# Digit.net
KiCad netlist of a schematic drawn in Altium Designer
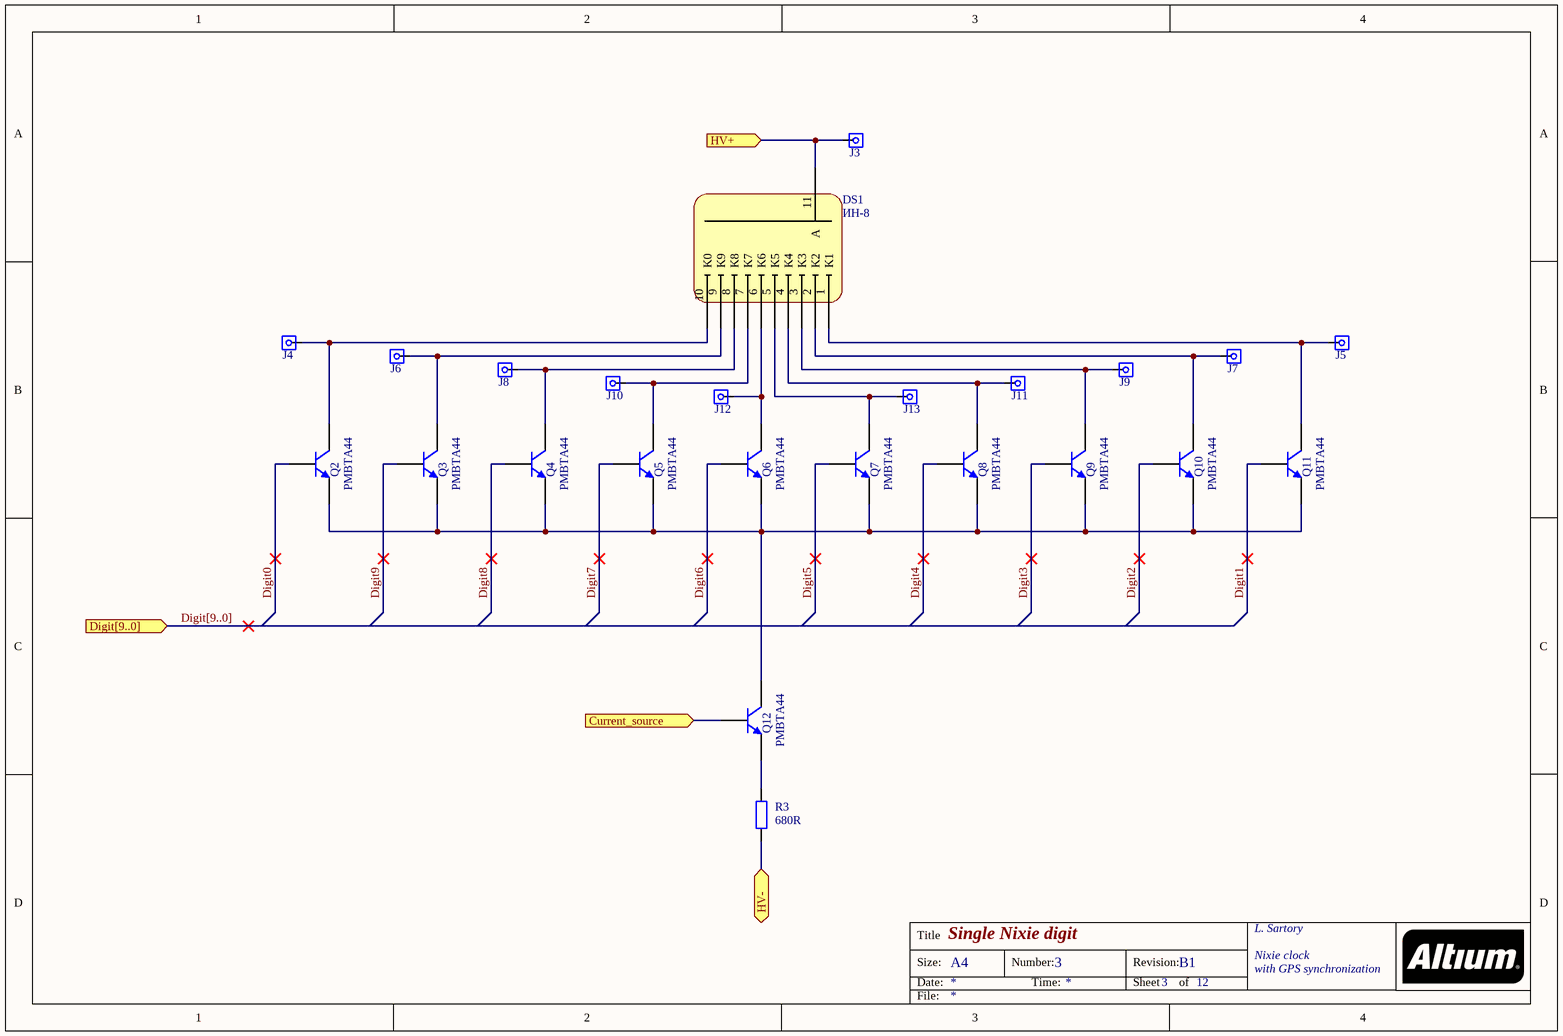
[diagram p0: Digit.SchDoc]

(export (version "E")
  (design (tool "Eeschema 10.0.6"))
  (components
    (comp (ref "DS1")
      (value "ИН-8")
      (footprint "IN-8")
      (description "Nixie tube")
      (libsource (lib "Nixie") (part "ИН-8"))
    )
    (comp (ref "J3")
      (value "TE_5645518-1")
      (footprint "TE_5645518-1")
      (description "Mini-spring socket")
      (libsource (lib "") (part "TE_5645518-1_1"))
    )
    (comp (ref "J4")
      (value "TE_5645518-1")
      (footprint "TE_5645518-1")
      (description "Mini-spring socket")
      (libsource (lib "Nixie") (part "TE_5645518-1"))
    )
    (comp (ref "J5")
      (value "TE_5645518-1")
      (footprint "TE_5645518-1")
      (description "Mini-spring socket")
      (libsource (lib "") (part "TE_5645518-1_1"))
    )
    (comp (ref "J6")
      (value "TE_5645518-1")
      (footprint "TE_5645518-1")
      (description "Mini-spring socket")
      (libsource (lib "Nixie") (part "TE_5645518-1"))
    )
    (comp (ref "J7")
      (value "TE_5645518-1")
      (footprint "TE_5645518-1")
      (description "Mini-spring socket")
      (libsource (lib "") (part "TE_5645518-1_1"))
    )
    (comp (ref "J8")
      (value "TE_5645518-1")
      (footprint "TE_5645518-1")
      (description "Mini-spring socket")
      (libsource (lib "Nixie") (part "TE_5645518-1"))
    )
    (comp (ref "J9")
      (value "TE_5645518-1")
      (footprint "TE_5645518-1")
      (description "Mini-spring socket")
      (libsource (lib "") (part "TE_5645518-1_1"))
    )
    (comp (ref "J10")
      (value "TE_5645518-1")
      (footprint "TE_5645518-1")
      (description "Mini-spring socket")
      (libsource (lib "Nixie") (part "TE_5645518-1"))
    )
    (comp (ref "J11")
      (value "TE_5645518-1")
      (footprint "TE_5645518-1")
      (description "Mini-spring socket")
      (libsource (lib "") (part "TE_5645518-1_1"))
    )
    (comp (ref "J12")
      (value "TE_5645518-1")
      (footprint "TE_5645518-1")
      (description "Mini-spring socket")
      (libsource (lib "Nixie") (part "TE_5645518-1"))
    )
    (comp (ref "J13")
      (value "TE_5645518-1")
      (footprint "TE_5645518-1")
      (description "Mini-spring socket")
      (libsource (lib "") (part "TE_5645518-1_1"))
    )
    (comp (ref "Q2")
      (value "PMBTA44")
      (footprint "SOT23_PMBTA44")
      (description "400 V, 0.3 A NPN high-voltage low VCEsat transistor")
      (libsource (lib "Nixie") (part "PMBTA44"))
    )
    (comp (ref "Q3")
      (value "PMBTA44")
      (footprint "SOT23_PMBTA44")
      (description "400 V, 0.3 A NPN high-voltage low VCEsat transistor")
      (libsource (lib "Nixie") (part "PMBTA44"))
    )
    (comp (ref "Q4")
      (value "PMBTA44")
      (footprint "SOT23_PMBTA44")
      (description "400 V, 0.3 A NPN high-voltage low VCEsat transistor")
      (libsource (lib "Nixie") (part "PMBTA44"))
    )
    (comp (ref "Q5")
      (value "PMBTA44")
      (footprint "SOT23_PMBTA44")
      (description "400 V, 0.3 A NPN high-voltage low VCEsat transistor")
      (libsource (lib "Nixie") (part "PMBTA44"))
    )
    (comp (ref "Q6")
      (value "PMBTA44")
      (footprint "SOT23_PMBTA44")
      (description "400 V, 0.3 A NPN high-voltage low VCEsat transistor")
      (libsource (lib "Nixie") (part "PMBTA44"))
    )
    (comp (ref "Q7")
      (value "PMBTA44")
      (footprint "SOT23_PMBTA44")
      (description "400 V, 0.3 A NPN high-voltage low VCEsat transistor")
      (libsource (lib "Nixie") (part "PMBTA44"))
    )
    (comp (ref "Q8")
      (value "PMBTA44")
      (footprint "SOT23_PMBTA44")
      (description "400 V, 0.3 A NPN high-voltage low VCEsat transistor")
      (libsource (lib "Nixie") (part "PMBTA44"))
    )
    (comp (ref "Q9")
      (value "PMBTA44")
      (footprint "SOT23_PMBTA44")
      (description "400 V, 0.3 A NPN high-voltage low VCEsat transistor")
      (libsource (lib "Nixie") (part "PMBTA44"))
    )
    (comp (ref "Q10")
      (value "PMBTA44")
      (footprint "SOT23_PMBTA44")
      (description "400 V, 0.3 A NPN high-voltage low VCEsat transistor")
      (libsource (lib "Nixie") (part "PMBTA44"))
    )
    (comp (ref "Q11")
      (value "PMBTA44")
      (footprint "SOT23_PMBTA44")
      (description "400 V, 0.3 A NPN high-voltage low VCEsat transistor")
      (libsource (lib "Nixie") (part "PMBTA44"))
    )
    (comp (ref "Q12")
      (value "PMBTA44")
      (footprint "SOT23_PMBTA44")
      (description "400 V, 0.3 A NPN high-voltage low VCEsat transistor")
      (libsource (lib "Nixie") (part "PMBTA44"))
    )
    (comp (ref "R3")
      (value "680R")
      (footprint "RES0805")
      (description "Chip resistor 680R 0805")
      (libsource (lib "Nixie") (part "680R 0805"))
    )
  )
  (nets
    (net (code "1") (name "/Current_source") (class "Default")
      (node (ref "Q12") (pin "1") (pinfunction "B_1") (pintype "passive"))
    )
    (net (code "2") (name "/Digit0") (class "Default")
      (node (ref "Q2") (pin "1") (pinfunction "B_1") (pintype "passive"))
    )
    (net (code "3") (name "/Digit1") (class "Default")
      (node (ref "Q11") (pin "1") (pinfunction "B_1") (pintype "passive"))
    )
    (net (code "4") (name "/Digit2") (class "Default")
      (node (ref "Q10") (pin "1") (pinfunction "B_1") (pintype "passive"))
    )
    (net (code "5") (name "/Digit3") (class "Default")
      (node (ref "Q9") (pin "1") (pinfunction "B_1") (pintype "passive"))
    )
    (net (code "6") (name "/Digit4") (class "Default")
      (node (ref "Q8") (pin "1") (pinfunction "B_1") (pintype "passive"))
    )
    (net (code "7") (name "/Digit5") (class "Default")
      (node (ref "Q7") (pin "1") (pinfunction "B_1") (pintype "passive"))
    )
    (net (code "8") (name "/Digit6") (class "Default")
      (node (ref "Q6") (pin "1") (pinfunction "B_1") (pintype "passive"))
    )
    (net (code "9") (name "/Digit7") (class "Default")
      (node (ref "Q5") (pin "1") (pinfunction "B_1") (pintype "passive"))
    )
    (net (code "10") (name "/Digit8") (class "Default")
      (node (ref "Q4") (pin "1") (pinfunction "B_1") (pintype "passive"))
    )
    (net (code "11") (name "/Digit9") (class "Default")
      (node (ref "Q3") (pin "1") (pinfunction "B_1") (pintype "passive"))
    )
    (net (code "13") (name "/HV+") (class "Default")
      (node (ref "DS1") (pin "11") (pinfunction "A_11") (pintype "passive"))
      (node (ref "J3") (pin "1") (pinfunction "1_1") (pintype "passive"))
    )
    (net (code "14") (name "/HV-") (class "Default")
      (node (ref "R3") (pin "1") (pinfunction "1_1") (pintype "passive"))
    )
    (net (code "15") (name "Net-(DS1-K0)") (class "Default")
      (node (ref "DS1") (pin "10") (pinfunction "K0_10") (pintype "passive"))
      (node (ref "J4") (pin "1") (pinfunction "1_1") (pintype "passive"))
      (node (ref "Q2") (pin "3") (pinfunction "C_3") (pintype "passive"))
    )
    (net (code "16") (name "Net-(DS1-K1)") (class "Default")
      (node (ref "DS1") (pin "1") (pinfunction "K1_1") (pintype "passive"))
      (node (ref "J5") (pin "1") (pinfunction "1_1") (pintype "passive"))
      (node (ref "Q11") (pin "3") (pinfunction "C_3") (pintype "passive"))
    )
    (net (code "17") (name "Net-(DS1-K2)") (class "Default")
      (node (ref "DS1") (pin "2") (pinfunction "K2_2") (pintype "passive"))
      (node (ref "J7") (pin "1") (pinfunction "1_1") (pintype "passive"))
      (node (ref "Q10") (pin "3") (pinfunction "C_3") (pintype "passive"))
    )
    (net (code "18") (name "Net-(DS1-K3)") (class "Default")
      (node (ref "DS1") (pin "3") (pinfunction "K3_3") (pintype "passive"))
      (node (ref "J9") (pin "1") (pinfunction "1_1") (pintype "passive"))
      (node (ref "Q9") (pin "3") (pinfunction "C_3") (pintype "passive"))
    )
    (net (code "19") (name "Net-(DS1-K4)") (class "Default")
      (node (ref "DS1") (pin "4") (pinfunction "K4_4") (pintype "passive"))
      (node (ref "J11") (pin "1") (pinfunction "1_1") (pintype "passive"))
      (node (ref "Q8") (pin "3") (pinfunction "C_3") (pintype "passive"))
    )
    (net (code "20") (name "Net-(DS1-K5)") (class "Default")
      (node (ref "DS1") (pin "5") (pinfunction "K5_5") (pintype "passive"))
      (node (ref "J13") (pin "1") (pinfunction "1_1") (pintype "passive"))
      (node (ref "Q7") (pin "3") (pinfunction "C_3") (pintype "passive"))
    )
    (net (code "21") (name "Net-(DS1-K6)") (class "Default")
      (node (ref "DS1") (pin "6") (pinfunction "K6_6") (pintype "passive"))
      (node (ref "J12") (pin "1") (pinfunction "1_1") (pintype "passive"))
      (node (ref "Q6") (pin "3") (pinfunction "C_3") (pintype "passive"))
    )
    (net (code "22") (name "Net-(DS1-K7)") (class "Default")
      (node (ref "DS1") (pin "7") (pinfunction "K7_7") (pintype "passive"))
      (node (ref "J10") (pin "1") (pinfunction "1_1") (pintype "passive"))
      (node (ref "Q5") (pin "3") (pinfunction "C_3") (pintype "passive"))
    )
    (net (code "23") (name "Net-(DS1-K8)") (class "Default")
      (node (ref "DS1") (pin "8") (pinfunction "K8_8") (pintype "passive"))
      (node (ref "J8") (pin "1") (pinfunction "1_1") (pintype "passive"))
      (node (ref "Q4") (pin "3") (pinfunction "C_3") (pintype "passive"))
    )
    (net (code "24") (name "Net-(DS1-K9)") (class "Default")
      (node (ref "DS1") (pin "9") (pinfunction "K9_9") (pintype "passive"))
      (node (ref "J6") (pin "1") (pinfunction "1_1") (pintype "passive"))
      (node (ref "Q3") (pin "3") (pinfunction "C_3") (pintype "passive"))
    )
    (net (code "25") (name "Net-(Q10-E)") (class "Default")
      (node (ref "Q10") (pin "2") (pinfunction "E_2") (pintype "passive"))
      (node (ref "Q11") (pin "2") (pinfunction "E_2") (pintype "passive"))
      (node (ref "Q12") (pin "3") (pinfunction "C_3") (pintype "passive"))
      (node (ref "Q2") (pin "2") (pinfunction "E_2") (pintype "passive"))
      (node (ref "Q3") (pin "2") (pinfunction "E_2") (pintype "passive"))
      (node (ref "Q4") (pin "2") (pinfunction "E_2") (pintype "passive"))
      (node (ref "Q5") (pin "2") (pinfunction "E_2") (pintype "passive"))
      (node (ref "Q6") (pin "2") (pinfunction "E_2") (pintype "passive"))
      (node (ref "Q7") (pin "2") (pinfunction "E_2") (pintype "passive"))
      (node (ref "Q8") (pin "2") (pinfunction "E_2") (pintype "passive"))
      (node (ref "Q9") (pin "2") (pinfunction "E_2") (pintype "passive"))
    )
    (net (code "26") (name "Net-(Q12-E)") (class "Default")
      (node (ref "Q12") (pin "2") (pinfunction "E_2") (pintype "passive"))
      (node (ref "R3") (pin "2") (pinfunction "2_2") (pintype "passive"))
    )
  )
)
